# JW24A10L_revD.net
KiCad netlist of a schematic drawn in EAGLE
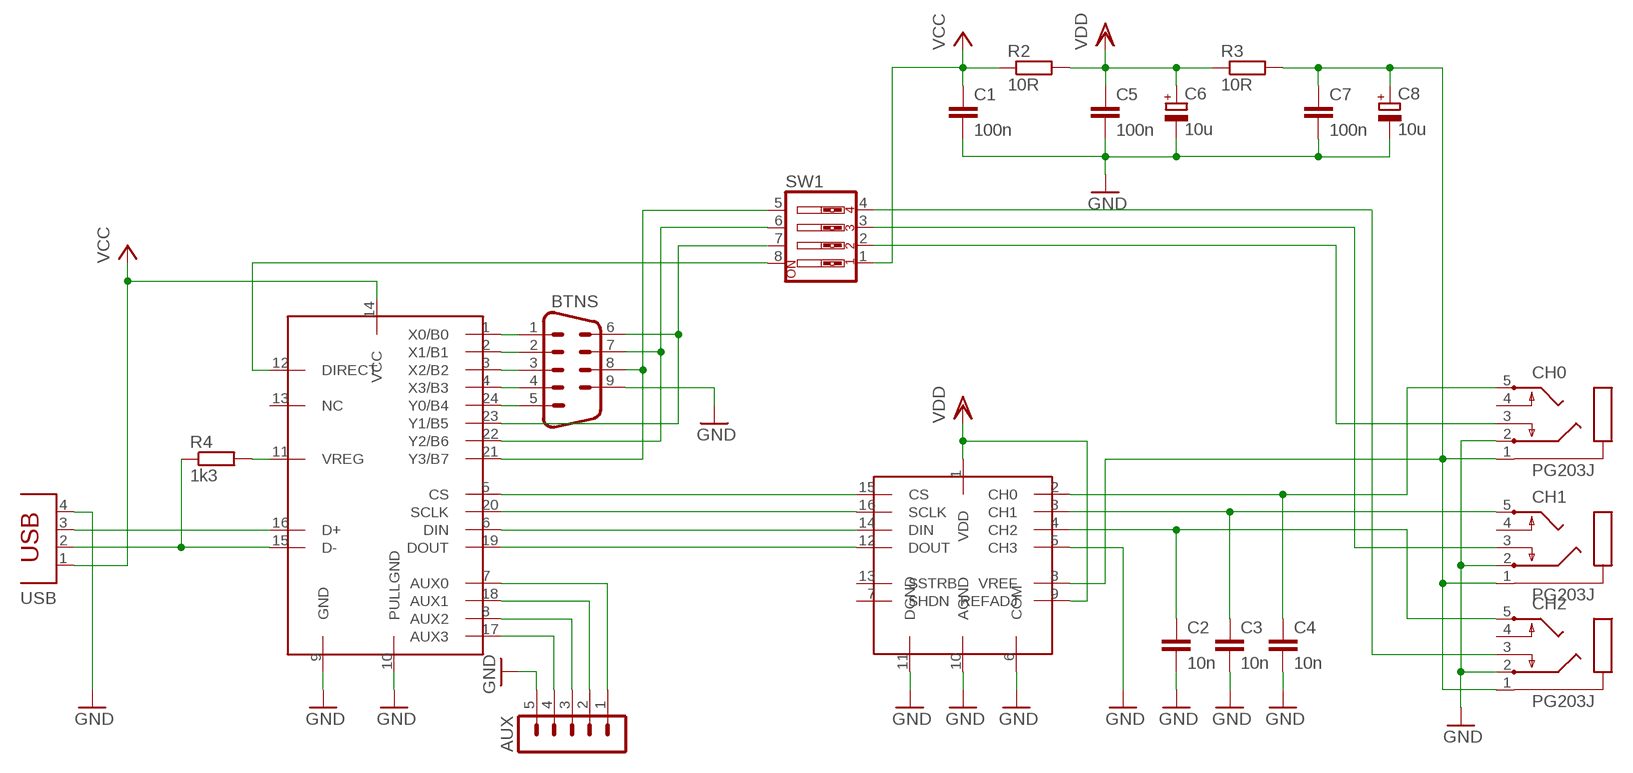
[diagram p0: schematic, sheet 1]

(export (version "E")
  (design (tool "Eeschema 10.0.6"))
  (components
    (comp (ref "AUX")
      (value "MA05-1")
      (footprint "eagle-import:MA05-1")
      (libsource (lib "eagle-import") (part "MA05-1"))
    )
    (comp (ref "BTNS")
      (value "M09H")
      (footprint "eagle-import:M09H")
      (libsource (lib "eagle-import") (part "M09H"))
    )
    (comp (ref "C1")
      (value "100n")
      (footprint "eagle-import:C025-025X050")
      (libsource (lib "eagle-import") (part "C-EU025-025X050"))
    )
    (comp (ref "C2")
      (value "10n")
      (footprint "eagle-import:C025-025X050")
      (libsource (lib "eagle-import") (part "C-EU025-025X050"))
    )
    (comp (ref "C3")
      (value "10n")
      (footprint "eagle-import:C025-025X050")
      (libsource (lib "eagle-import") (part "C-EU025-025X050"))
    )
    (comp (ref "C4")
      (value "10n")
      (footprint "eagle-import:C025-025X050")
      (libsource (lib "eagle-import") (part "C-EU025-025X050"))
    )
    (comp (ref "C5")
      (value "100n")
      (footprint "eagle-import:C025-025X050")
      (libsource (lib "eagle-import") (part "C-EU025-025X050"))
    )
    (comp (ref "C6")
      (value "10u")
      (footprint "eagle-import:E2-5")
      (libsource (lib "eagle-import") (part "CPOL-EUE2-5"))
    )
    (comp (ref "C7")
      (value "100n")
      (footprint "eagle-import:C025-025X050")
      (libsource (lib "eagle-import") (part "C-EU025-025X050"))
    )
    (comp (ref "C8")
      (value "10u")
      (footprint "eagle-import:E2-5")
      (libsource (lib "eagle-import") (part "CPOL-EUE2-5"))
    )
    (comp (ref "CH0")
      (value "PG203J")
      (footprint "eagle-import:PG203J")
      (libsource (lib "eagle-import") (part "PG203J"))
    )
    (comp (ref "CH1")
      (value "PG203J")
      (footprint "eagle-import:PG203J")
      (libsource (lib "eagle-import") (part "PG203J"))
    )
    (comp (ref "CH2")
      (value "PG203J")
      (footprint "eagle-import:PG203J")
      (libsource (lib "eagle-import") (part "PG203J"))
    )
    (comp (ref "R2")
      (value "10R")
      (footprint "eagle-import:0207_2V")
      (libsource (lib "eagle-import") (part "R-EU_0207/2V"))
    )
    (comp (ref "R3")
      (value "10R")
      (footprint "eagle-import:0207_2V")
      (libsource (lib "eagle-import") (part "R-EU_0207/2V"))
    )
    (comp (ref "R4")
      (value "1k3")
      (footprint "eagle-import:0207_2V")
      (libsource (lib "eagle-import") (part "R-EU_0207/2V"))
    )
    (comp (ref "SW1")
      (value "SW_DIP-4")
      (footprint "eagle-import:EDG-04")
      (libsource (lib "eagle-import") (part "SW_DIP-4"))
    )
    (comp (ref "U$1")
      (value "MAX1249")
      (footprint "eagle-import:DIL16")
      (libsource (lib "eagle-import") (part "MAX1249"))
    )
    (comp (ref "U$2")
      (value "JW24A10L")
      (footprint "eagle-import:DIL24-3")
      (libsource (lib "eagle-import") (part "JW24A10L"))
    )
    (comp (ref "USB")
      (value "PN61729")
      (footprint "eagle-import:PN61729")
      (libsource (lib "eagle-import") (part "PN61729"))
    )
  )
  (nets
    (net (code "1") (name "GND") (class "Default")
      (node (ref "AUX") (pin "5") (pinfunction "5_5") (pintype "passive"))
      (node (ref "BTNS") (pin "9") (pinfunction "9_9") (pintype "passive"))
      (node (ref "C1") (pin "2") (pinfunction "2_2") (pintype "passive"))
      (node (ref "C2") (pin "2") (pinfunction "2_2") (pintype "passive"))
      (node (ref "C3") (pin "2") (pinfunction "2_2") (pintype "passive"))
      (node (ref "C4") (pin "2") (pinfunction "2_2") (pintype "passive"))
      (node (ref "C5") (pin "2") (pinfunction "2_2") (pintype "passive"))
      (node (ref "C6") (pin "-") (pinfunction "-_-") (pintype "passive"))
      (node (ref "C7") (pin "2") (pinfunction "2_2") (pintype "passive"))
      (node (ref "C8") (pin "-") (pinfunction "-_-") (pintype "passive"))
      (node (ref "CH0") (pin "2") (pinfunction "2_2") (pintype "passive"))
      (node (ref "CH1") (pin "2") (pinfunction "2_2") (pintype "passive"))
      (node (ref "CH2") (pin "2") (pinfunction "2_2") (pintype "passive"))
      (node (ref "U$1") (pin "10") (pinfunction "AGND_10") (pintype "power_in"))
      (node (ref "U$1") (pin "11") (pinfunction "DGND_11") (pintype "power_in"))
      (node (ref "U$1") (pin "5") (pinfunction "CH3_5") (pintype "input"))
      (node (ref "U$1") (pin "6") (pinfunction "COM_6") (pintype "bidirectional"))
      (node (ref "U$2") (pin "10") (pinfunction "PULLGND_10") (pintype "power_in"))
      (node (ref "U$2") (pin "9") (pinfunction "GND_9") (pintype "power_in"))
      (node (ref "USB") (pin "4") (pinfunction "4_4") (pintype "passive"))
    )
    (net (code "2") (name "Net-(CH0-Pad3)") (class "Default")
      (node (ref "CH0") (pin "3") (pinfunction "3_3") (pintype "passive"))
      (node (ref "SW1") (pin "2") (pinfunction "2_2") (pintype "passive"))
    )
    (net (code "3") (name "Net-(CH1-Pad3)") (class "Default")
      (node (ref "CH1") (pin "3") (pinfunction "3_3") (pintype "passive"))
      (node (ref "SW1") (pin "3") (pinfunction "3_3") (pintype "passive"))
    )
    (net (code "4") (name "Net-(CH2-Pad3)") (class "Default")
      (node (ref "CH2") (pin "3") (pinfunction "3_3") (pintype "passive"))
      (node (ref "SW1") (pin "4") (pinfunction "4_4") (pintype "passive"))
    )
    (net (code "5") (name "Net-(U$1-CH0)") (class "Default")
      (node (ref "C4") (pin "1") (pinfunction "1_1") (pintype "passive"))
      (node (ref "CH0") (pin "5") (pinfunction "5_5") (pintype "passive"))
      (node (ref "U$1") (pin "2") (pinfunction "CH0_2") (pintype "input"))
    )
    (net (code "6") (name "Net-(U$1-CH1)") (class "Default")
      (node (ref "C3") (pin "1") (pinfunction "1_1") (pintype "passive"))
      (node (ref "CH1") (pin "5") (pinfunction "5_5") (pintype "passive"))
      (node (ref "U$1") (pin "3") (pinfunction "CH1_3") (pintype "input"))
    )
    (net (code "7") (name "Net-(U$1-CH2)") (class "Default")
      (node (ref "C2") (pin "1") (pinfunction "1_1") (pintype "passive"))
      (node (ref "CH2") (pin "5") (pinfunction "5_5") (pintype "passive"))
      (node (ref "U$1") (pin "4") (pinfunction "CH2_4") (pintype "input"))
    )
    (net (code "8") (name "Net-(U$1-CS)") (class "Default")
      (node (ref "U$1") (pin "15") (pinfunction "CS_15") (pintype "bidirectional"))
      (node (ref "U$2") (pin "5") (pinfunction "CS_5") (pintype "bidirectional"))
    )
    (net (code "9") (name "Net-(U$1-DIN)") (class "Default")
      (node (ref "U$1") (pin "14") (pinfunction "DIN_14") (pintype "bidirectional"))
      (node (ref "U$2") (pin "6") (pinfunction "DIN_6") (pintype "bidirectional"))
    )
    (net (code "10") (name "Net-(U$1-DOUT)") (class "Default")
      (node (ref "U$1") (pin "12") (pinfunction "DOUT_12") (pintype "bidirectional"))
      (node (ref "U$2") (pin "19") (pinfunction "DOUT_19") (pintype "bidirectional"))
    )
    (net (code "11") (name "Net-(U$1-SCLK)") (class "Default")
      (node (ref "U$1") (pin "16") (pinfunction "SCLK_16") (pintype "bidirectional"))
      (node (ref "U$2") (pin "20") (pinfunction "SCLK_20") (pintype "bidirectional"))
    )
    (net (code "12") (name "Net-(U$1-VREF)") (class "Default")
      (node (ref "C7") (pin "1") (pinfunction "1_1") (pintype "passive"))
      (node (ref "C8") (pin "+") (pinfunction "+_+") (pintype "passive"))
      (node (ref "CH0") (pin "1") (pinfunction "1_1") (pintype "passive"))
      (node (ref "CH1") (pin "1") (pinfunction "1_1") (pintype "passive"))
      (node (ref "CH2") (pin "1") (pinfunction "1_1") (pintype "passive"))
      (node (ref "R3") (pin "2") (pinfunction "2_2") (pintype "passive"))
      (node (ref "U$1") (pin "8") (pinfunction "VREF_8") (pintype "bidirectional"))
    )
    (net (code "13") (name "Net-(U$2-AUX0)") (class "Default")
      (node (ref "AUX") (pin "1") (pinfunction "1_1") (pintype "passive"))
      (node (ref "U$2") (pin "7") (pinfunction "AUX0_7") (pintype "power_in"))
    )
    (net (code "14") (name "Net-(U$2-AUX1)") (class "Default")
      (node (ref "AUX") (pin "2") (pinfunction "2_2") (pintype "passive"))
      (node (ref "U$2") (pin "18") (pinfunction "AUX1_18") (pintype "power_in"))
    )
    (net (code "15") (name "Net-(U$2-AUX2)") (class "Default")
      (node (ref "AUX") (pin "3") (pinfunction "3_3") (pintype "passive"))
      (node (ref "U$2") (pin "8") (pinfunction "AUX2_8") (pintype "power_in"))
    )
    (net (code "16") (name "Net-(U$2-AUX3)") (class "Default")
      (node (ref "AUX") (pin "4") (pinfunction "4_4") (pintype "passive"))
      (node (ref "U$2") (pin "17") (pinfunction "AUX3_17") (pintype "power_in"))
    )
    (net (code "17") (name "Net-(U$2-D+)") (class "Default")
      (node (ref "U$2") (pin "16") (pinfunction "D+_16") (pintype "bidirectional"))
      (node (ref "USB") (pin "3") (pinfunction "3_3") (pintype "passive"))
    )
    (net (code "18") (name "Net-(U$2-D-)") (class "Default")
      (node (ref "R4") (pin "1") (pinfunction "1_1") (pintype "passive"))
      (node (ref "U$2") (pin "15") (pinfunction "D-_15") (pintype "bidirectional"))
      (node (ref "USB") (pin "2") (pinfunction "2_2") (pintype "passive"))
    )
    (net (code "19") (name "Net-(U$2-DIRECT)") (class "Default")
      (node (ref "SW1") (pin "8") (pinfunction "8_8") (pintype "passive"))
      (node (ref "U$2") (pin "12") (pinfunction "DIRECT_12") (pintype "bidirectional"))
    )
    (net (code "20") (name "Net-(U$2-VREG)") (class "Default")
      (node (ref "R4") (pin "2") (pinfunction "2_2") (pintype "passive"))
      (node (ref "U$2") (pin "11") (pinfunction "VREG_11") (pintype "bidirectional"))
    )
    (net (code "21") (name "Net-(U$2-X0{slash}B0)") (class "Default")
      (node (ref "BTNS") (pin "1") (pinfunction "1_1") (pintype "passive"))
      (node (ref "U$2") (pin "1") (pinfunction "X0/B0_1") (pintype "bidirectional"))
    )
    (net (code "22") (name "Net-(U$2-X1{slash}B1)") (class "Default")
      (node (ref "BTNS") (pin "2") (pinfunction "2_2") (pintype "passive"))
      (node (ref "U$2") (pin "2") (pinfunction "X1/B1_2") (pintype "bidirectional"))
    )
    (net (code "23") (name "Net-(U$2-X2{slash}B2)") (class "Default")
      (node (ref "BTNS") (pin "3") (pinfunction "3_3") (pintype "passive"))
      (node (ref "U$2") (pin "3") (pinfunction "X2/B2_3") (pintype "bidirectional"))
    )
    (net (code "24") (name "Net-(U$2-X3{slash}B3)") (class "Default")
      (node (ref "BTNS") (pin "4") (pinfunction "4_4") (pintype "passive"))
      (node (ref "U$2") (pin "4") (pinfunction "X3/B3_4") (pintype "bidirectional"))
    )
    (net (code "25") (name "Net-(U$2-Y0{slash}B4)") (class "Default")
      (node (ref "BTNS") (pin "5") (pinfunction "5_5") (pintype "passive"))
      (node (ref "U$2") (pin "24") (pinfunction "Y0/B4_24") (pintype "bidirectional"))
    )
    (net (code "26") (name "Net-(U$2-Y1{slash}B5)") (class "Default")
      (node (ref "BTNS") (pin "6") (pinfunction "6_6") (pintype "passive"))
      (node (ref "SW1") (pin "7") (pinfunction "7_7") (pintype "passive"))
      (node (ref "U$2") (pin "23") (pinfunction "Y1/B5_23") (pintype "bidirectional"))
    )
    (net (code "27") (name "Net-(U$2-Y2{slash}B6)") (class "Default")
      (node (ref "BTNS") (pin "7") (pinfunction "7_7") (pintype "passive"))
      (node (ref "SW1") (pin "6") (pinfunction "6_6") (pintype "passive"))
      (node (ref "U$2") (pin "22") (pinfunction "Y2/B6_22") (pintype "bidirectional"))
    )
    (net (code "28") (name "Net-(U$2-Y3{slash}B7)") (class "Default")
      (node (ref "BTNS") (pin "8") (pinfunction "8_8") (pintype "passive"))
      (node (ref "SW1") (pin "5") (pinfunction "5_5") (pintype "passive"))
      (node (ref "U$2") (pin "21") (pinfunction "Y3/B7_21") (pintype "bidirectional"))
    )
    (net (code "29") (name "VCC") (class "Default")
      (node (ref "C1") (pin "1") (pinfunction "1_1") (pintype "passive"))
      (node (ref "R2") (pin "1") (pinfunction "1_1") (pintype "passive"))
      (node (ref "SW1") (pin "1") (pinfunction "1_1") (pintype "passive"))
      (node (ref "U$2") (pin "14") (pinfunction "VCC_14") (pintype "power_in"))
      (node (ref "USB") (pin "1") (pinfunction "1_1") (pintype "passive"))
    )
    (net (code "30") (name "VDD") (class "Default")
      (node (ref "C5") (pin "1") (pinfunction "1_1") (pintype "passive"))
      (node (ref "C6") (pin "+") (pinfunction "+_+") (pintype "passive"))
      (node (ref "R2") (pin "2") (pinfunction "2_2") (pintype "passive"))
      (node (ref "R3") (pin "1") (pinfunction "1_1") (pintype "passive"))
      (node (ref "U$1") (pin "1") (pinfunction "VDD_1") (pintype "power_in"))
      (node (ref "U$1") (pin "9") (pinfunction "REFADJ_9") (pintype "bidirectional"))
    )
    (net (code "31") (name "unconnected-(CH0-Pad4)") (class "Default")
      (node (ref "CH0") (pin "4") (pinfunction "4_4") (pintype "passive"))
    )
    (net (code "32") (name "unconnected-(CH1-Pad4)") (class "Default")
      (node (ref "CH1") (pin "4") (pinfunction "4_4") (pintype "passive"))
    )
    (net (code "33") (name "unconnected-(CH2-Pad4)") (class "Default")
      (node (ref "CH2") (pin "4") (pinfunction "4_4") (pintype "passive"))
    )
    (net (code "34") (name "unconnected-(U$1-SHDN-Pad7)") (class "Default")
      (node (ref "U$1") (pin "7") (pinfunction "SHDN_7") (pintype "bidirectional"))
    )
    (net (code "35") (name "unconnected-(U$1-SSTRB-Pad13)") (class "Default")
      (node (ref "U$1") (pin "13") (pinfunction "SSTRB_13") (pintype "bidirectional"))
    )
    (net (code "36") (name "unconnected-(U$2-NC-Pad13)") (class "Default")
      (node (ref "U$2") (pin "13") (pinfunction "NC_13") (pintype "bidirectional"))
    )
  )
)
